# Sheet_v3.net
KiCad netlist of a schematic drawn in Altium Designer
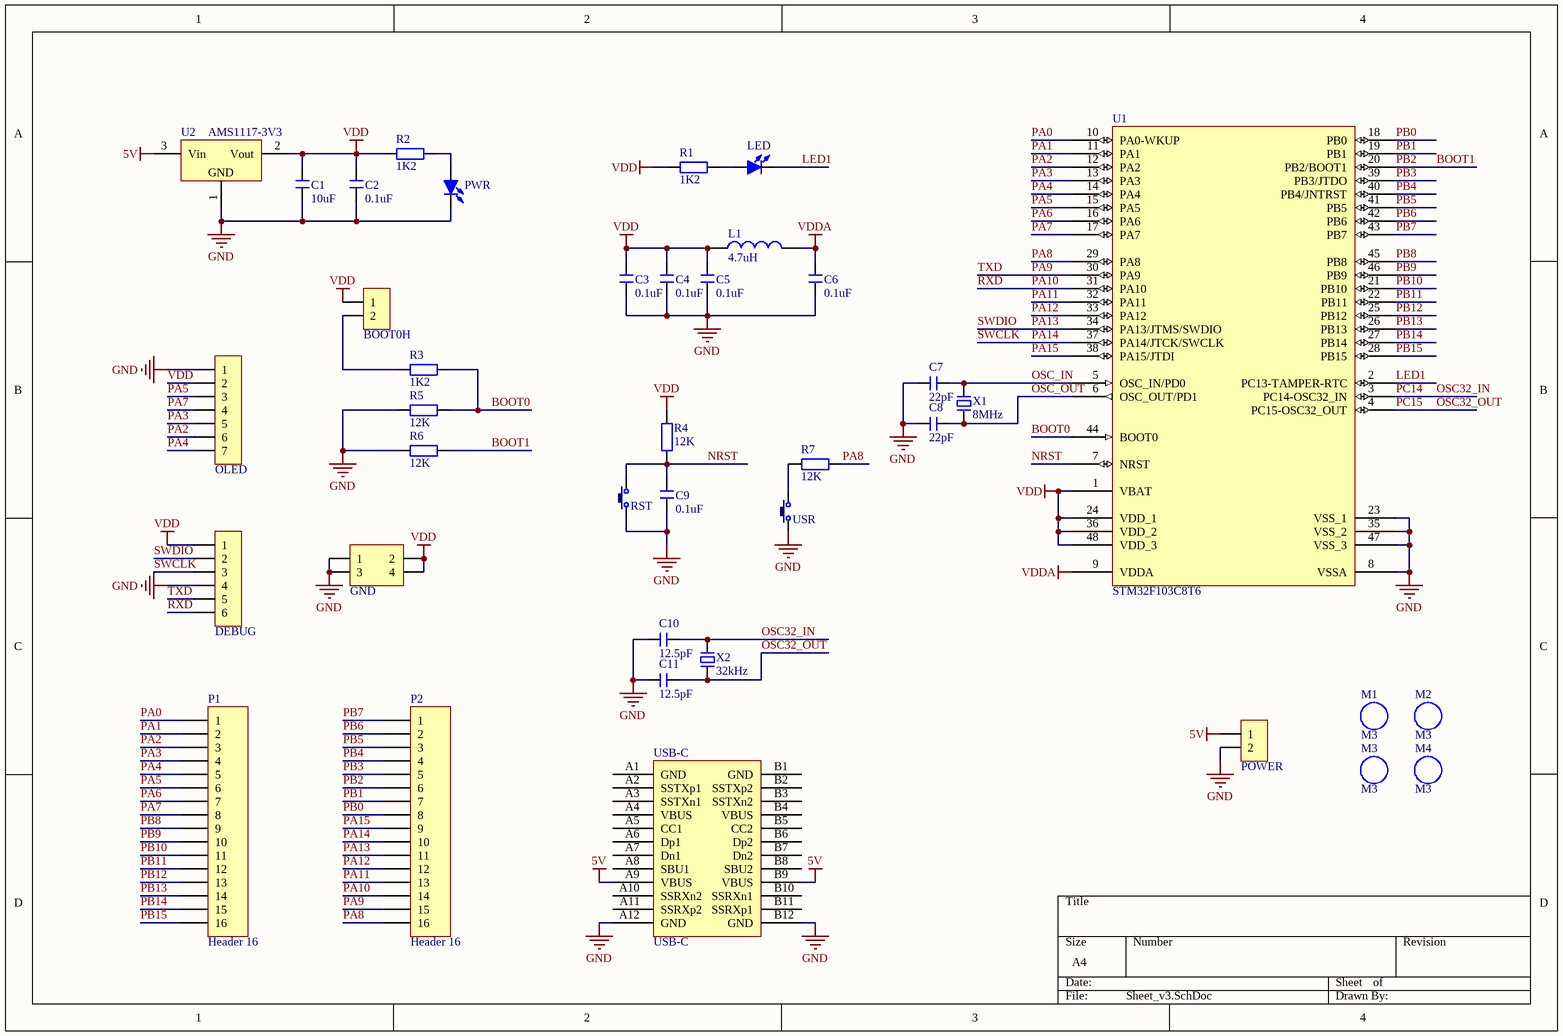
[diagram p0: Sheet_v3.SchDoc]

(export (version "E")
  (design (tool "Eeschema 10.0.6"))
  (components
    (comp (ref "BOOT0H")
      (value "HDR-1X2")
      (footprint "TSW SMD-3*4*2.5")
      (description "2P接插件")
      (fields (field (name "版权归属") "源创客"))
      (libsource (lib "接插件") (part "Header 2"))
    )
    (comp (ref "C1")
      (value "10uF")
      (footprint "C 0805")
      (description "无极性贴片电容")
      (fields (field (name "版权归属") "源创客"))
      (libsource (lib "电阻-电容-电感") (part "C"))
    )
    (comp (ref "C2")
      (value "0.1uF")
      (footprint "C 0603")
      (description "无极性贴片电容")
      (fields (field (name "版权归属") "源创客"))
      (libsource (lib "电阻-电容-电感") (part "C"))
    )
    (comp (ref "C3")
      (value "0.1uF")
      (footprint "C 0603")
      (description "无极性贴片电容")
      (fields (field (name "版权归属") "源创客"))
      (libsource (lib "电阻-电容-电感") (part "C"))
    )
    (comp (ref "C4")
      (value "0.1uF")
      (footprint "C 0603")
      (description "无极性贴片电容")
      (fields (field (name "版权归属") "源创客"))
      (libsource (lib "电阻-电容-电感") (part "C"))
    )
    (comp (ref "C5")
      (value "0.1uF")
      (footprint "C 0603")
      (description "无极性贴片电容")
      (fields (field (name "版权归属") "源创客"))
      (libsource (lib "电阻-电容-电感") (part "C"))
    )
    (comp (ref "C6")
      (value "0.1uF")
      (footprint "C 0603")
      (description "无极性贴片电容")
      (fields (field (name "版权归属") "源创客"))
      (libsource (lib "电阻-电容-电感") (part "C"))
    )
    (comp (ref "C7")
      (value "22pF")
      (footprint "C 0603")
      (description "无极性贴片电容")
      (fields (field (name "版权归属") "源创客"))
      (libsource (lib "电阻-电容-电感") (part "C"))
    )
    (comp (ref "C8")
      (value "22pF")
      (footprint "C 0603")
      (description "无极性贴片电容")
      (fields (field (name "版权归属") "源创客"))
      (libsource (lib "电阻-电容-电感") (part "C"))
    )
    (comp (ref "C9")
      (value "0.1uF")
      (footprint "C 0603")
      (description "无极性贴片电容")
      (fields (field (name "版权归属") "源创客"))
      (libsource (lib "电阻-电容-电感") (part "C"))
    )
    (comp (ref "C10")
      (value "12.5pF")
      (footprint "C 0603")
      (description "无极性贴片电容")
      (fields (field (name "版权归属") "源创客"))
      (libsource (lib "电阻-电容-电感") (part "C"))
    )
    (comp (ref "C11")
      (value "12.5pF")
      (footprint "C 0603")
      (description "无极性贴片电容")
      (fields (field (name "版权归属") "源创客"))
      (libsource (lib "电阻-电容-电感") (part "C"))
    )
    (comp (ref "DEBUG")
      (value "HDR-1X6")
      (footprint "HDR-1X6")
      (description "6P接插件")
      (fields (field (name "版权归属") "源创客"))
      (libsource (lib "接插件") (part "Header 6"))
    )
    (comp (ref "GND")
      (value "Header2X2")
      (footprint "HDR-2X2")
      (description "2*2P接插件")
      (fields (field (name "版权归属") "源创客"))
      (libsource (lib "接插件") (part "Header 2X2"))
    )
    (comp (ref "L1")
      (value "4.7uH")
      (footprint "L 0805")
      (description "小功率贴片电感")
      (fields (field (name "版权归属") "源创客"))
      (libsource (lib "电阻-电容-电感") (part "L"))
    )
    (comp (ref "LED")
      (value "~")
      (footprint "LED 0805G")
      (description "贴片LED")
      (fields (field (name "版权归属") "源创客"))
      (libsource (lib "LED") (part "LED-SMD"))
    )
    (comp (ref "M1")
      (value "M3")
      (footprint "M3 125X200")
      (description "铜柱孔")
      (fields (field (name "版权归属") "源创客"))
      (libsource (lib "未分类器件") (part "M3"))
    )
    (comp (ref "M2")
      (value "M3")
      (footprint "M3 125X200")
      (description "铜柱孔")
      (fields (field (name "版权归属") "源创客"))
      (libsource (lib "未分类器件") (part "M3"))
    )
    (comp (ref "M3")
      (value "M3")
      (footprint "M3 125X200")
      (description "铜柱孔")
      (fields (field (name "版权归属") "源创客"))
      (libsource (lib "未分类器件") (part "M3"))
    )
    (comp (ref "M4")
      (value "M3")
      (footprint "M3 125X200")
      (description "铜柱孔")
      (fields (field (name "版权归属") "源创客"))
      (libsource (lib "未分类器件") (part "M3"))
    )
    (comp (ref "OLED")
      (value "HDR-1X7")
      (footprint "HDR-1X7_M")
      (description "7P接插件")
      (fields (field (name "版权归属") "源创客"))
      (libsource (lib "接插件") (part "Header 7"))
    )
    (comp (ref "P1")
      (value "Header 16")
      (footprint "HDR1X16")
      (description "Header, 16-Pin")
      (fields (field (name "PUBLISHER") "Altium Limited"))
      (libsource (lib "Miscellaneous Connectors") (part "Header 16"))
    )
    (comp (ref "P2")
      (value "Header 16")
      (footprint "HDR1X16")
      (description "Header, 16-Pin")
      (fields (field (name "PUBLISHER") "Altium Limited"))
      (libsource (lib "Miscellaneous Connectors") (part "Header 16"))
    )
    (comp (ref "POWER")
      (value "HDR-1X2")
      (footprint "HDR-1X2")
      (description "2P接插件")
      (fields (field (name "版权归属") "源创客"))
      (libsource (lib "接插件") (part "Header 2"))
    )
    (comp (ref "PWR")
      (value "~")
      (footprint "LED 0805G")
      (description "贴片LED")
      (fields (field (name "版权归属") "源创客"))
      (libsource (lib "LED") (part "LED-SMD"))
    )
    (comp (ref "R1")
      (value "1K2")
      (footprint "R 0805")
      (description "贴片电阻")
      (fields (field (name "版权归属") "源创客"))
      (libsource (lib "电阻-电容-电感") (part "R"))
    )
    (comp (ref "R2")
      (value "1K2")
      (footprint "R 0805")
      (description "贴片电阻")
      (fields (field (name "版权归属") "源创客"))
      (libsource (lib "电阻-电容-电感") (part "R"))
    )
    (comp (ref "R3")
      (value "1K2")
      (footprint "R 0805")
      (description "贴片电阻")
      (fields (field (name "版权归属") "源创客"))
      (libsource (lib "电阻-电容-电感") (part "R"))
    )
    (comp (ref "R4")
      (value "12K")
      (footprint "R 0805")
      (description "贴片电阻")
      (fields (field (name "版权归属") "源创客"))
      (libsource (lib "电阻-电容-电感") (part "R"))
    )
    (comp (ref "R5")
      (value "12K")
      (footprint "R 0805")
      (description "贴片电阻")
      (fields (field (name "版权归属") "源创客"))
      (libsource (lib "电阻-电容-电感") (part "R"))
    )
    (comp (ref "R6")
      (value "12K")
      (footprint "R 0805")
      (description "贴片电阻")
      (fields (field (name "版权归属") "源创客"))
      (libsource (lib "电阻-电容-电感") (part "R"))
    )
    (comp (ref "R7")
      (value "12K")
      (footprint "R 0805")
      (description "贴片电阻")
      (fields (field (name "版权归属") "源创客"))
      (libsource (lib "电阻-电容-电感") (part "R"))
    )
    (comp (ref "RST")
      (value "3x6x5")
      (footprint "TSW SMD-3*6*2.5")
      (description "3x6轻触开关")
      (fields (field (name "版权归属") "源创客"))
      (libsource (lib "按键-开关") (part "TSW 3x6"))
    )
    (comp (ref "U1")
      (value "STM32F103C8T6")
      (footprint "LQFP48 7X7_M")
      (description "Flaah:64/RAM:20/IO:36")
      (fields (field (name "版权归属") "源创客"))
      (libsource (lib "STM32系列单片机") (part "STM32F103C8T6"))
    )
    (comp (ref "U2")
      (value "AMS1117-3V3")
      (footprint "SOT223_M")
      (description "三端稳压芯片")
      (fields (field (name "版权归属") "源创客"))
      (libsource (lib "IC芯片") (part "AMS1117"))
    )
    (comp (ref "USB-C")
      (value "USB-C")
      (footprint "Type_C-6P")
      (description "USB-C型母接口")
      (fields (field (name "版权归属") "源创客"))
      (libsource (lib "接口类") (part "USB-C/S"))
    )
    (comp (ref "USR")
      (value "3x6x5")
      (footprint "TSW SMD-3*6*2.5")
      (description "3x6轻触开关")
      (fields (field (name "版权归属") "源创客"))
      (libsource (lib "按键-开关") (part "TSW 3x6"))
    )
    (comp (ref "X1")
      (value "8MHz")
      (footprint "XTAL-5032_2P")
      (description "2脚晶振")
      (fields (field (name "版权归属") "源创客"))
      (libsource (lib "保险丝-晶振") (part "XTAL-2"))
    )
    (comp (ref "X2")
      (value "32kHz")
      (footprint "XTAL-3215")
      (description "2脚晶振")
      (fields (field (name "版权归属") "源创客"))
      (libsource (lib "保险丝-晶振") (part "XTAL-2"))
    )
  )
  (nets
    (net (code "1") (name "/BOOT0") (class "Default")
      (node (ref "R3") (pin "1") (pinfunction "1_1") (pintype "passive"))
      (node (ref "R5") (pin "1") (pinfunction "1_1") (pintype "passive"))
      (node (ref "U1") (pin "44") (pinfunction "BOOT0_44") (pintype "input"))
    )
    (net (code "2") (name "/BOOT1") (class "Default")
      (node (ref "P2") (pin "6") (pinfunction "6_6") (pintype "passive"))
      (node (ref "R6") (pin "1") (pinfunction "1_1") (pintype "passive"))
      (node (ref "U1") (pin "20") (pinfunction "PB2/BOOT1_20") (pintype "bidirectional"))
    )
    (net (code "3") (name "/LED1") (class "Default")
      (node (ref "LED") (pin "2") (pinfunction "K_2") (pintype "passive"))
      (node (ref "U1") (pin "2") (pinfunction "PC13-TAMPER-RTC_2") (pintype "bidirectional"))
    )
    (net (code "4") (name "/NRST") (class "Default")
      (node (ref "C9") (pin "2") (pinfunction "2_2") (pintype "passive"))
      (node (ref "R4") (pin "1") (pinfunction "1_1") (pintype "passive"))
      (node (ref "RST") (pin "2") (pinfunction "2_2") (pintype "passive"))
      (node (ref "U1") (pin "7") (pinfunction "NRST_7") (pintype "bidirectional"))
    )
    (net (code "5") (name "/OSC32_IN") (class "Default")
      (node (ref "C10") (pin "2") (pinfunction "2_2") (pintype "passive"))
      (node (ref "U1") (pin "3") (pinfunction "PC14-OSC32_IN_3") (pintype "bidirectional"))
      (node (ref "X2") (pin "2") (pinfunction "2_2") (pintype "passive"))
    )
    (net (code "6") (name "/OSC32_OUT") (class "Default")
      (node (ref "C11") (pin "2") (pinfunction "2_2") (pintype "passive"))
      (node (ref "U1") (pin "4") (pinfunction "PC15-OSC32_OUT_4") (pintype "bidirectional"))
      (node (ref "X2") (pin "1") (pinfunction "1_1") (pintype "passive"))
    )
    (net (code "7") (name "/OSC_IN") (class "Default")
      (node (ref "C7") (pin "2") (pinfunction "2_2") (pintype "passive"))
      (node (ref "U1") (pin "5") (pinfunction "OSC_IN/PD0_5") (pintype "input"))
      (node (ref "X1") (pin "2") (pinfunction "2_2") (pintype "passive"))
    )
    (net (code "8") (name "/OSC_OUT") (class "Default")
      (node (ref "C8") (pin "2") (pinfunction "2_2") (pintype "passive"))
      (node (ref "U1") (pin "6") (pinfunction "OSC_OUT/PD1_6") (pintype "output"))
      (node (ref "X1") (pin "1") (pinfunction "1_1") (pintype "passive"))
    )
    (net (code "9") (name "/PA0") (class "Default")
      (node (ref "P1") (pin "1") (pinfunction "1_1") (pintype "passive"))
      (node (ref "U1") (pin "10") (pinfunction "PA0-WKUP_10") (pintype "bidirectional"))
    )
    (net (code "10") (name "/PA1") (class "Default")
      (node (ref "P1") (pin "2") (pinfunction "2_2") (pintype "passive"))
      (node (ref "U1") (pin "11") (pinfunction "PA1_11") (pintype "bidirectional"))
    )
    (net (code "11") (name "/PA2") (class "Default")
      (node (ref "OLED") (pin "6") (pinfunction "6_6") (pintype "passive"))
      (node (ref "P1") (pin "3") (pinfunction "3_3") (pintype "passive"))
      (node (ref "U1") (pin "12") (pinfunction "PA2_12") (pintype "bidirectional"))
    )
    (net (code "12") (name "/PA3") (class "Default")
      (node (ref "OLED") (pin "5") (pinfunction "5_5") (pintype "passive"))
      (node (ref "P1") (pin "4") (pinfunction "4_4") (pintype "passive"))
      (node (ref "U1") (pin "13") (pinfunction "PA3_13") (pintype "bidirectional"))
    )
    (net (code "13") (name "/PA4") (class "Default")
      (node (ref "OLED") (pin "7") (pinfunction "7_7") (pintype "passive"))
      (node (ref "P1") (pin "5") (pinfunction "5_5") (pintype "passive"))
      (node (ref "U1") (pin "14") (pinfunction "PA4_14") (pintype "bidirectional"))
    )
    (net (code "14") (name "/PA5") (class "Default")
      (node (ref "OLED") (pin "3") (pinfunction "3_3") (pintype "passive"))
      (node (ref "P1") (pin "6") (pinfunction "6_6") (pintype "passive"))
      (node (ref "U1") (pin "15") (pinfunction "PA5_15") (pintype "bidirectional"))
    )
    (net (code "15") (name "/PA6") (class "Default")
      (node (ref "P1") (pin "7") (pinfunction "7_7") (pintype "passive"))
      (node (ref "U1") (pin "16") (pinfunction "PA6_16") (pintype "bidirectional"))
    )
    (net (code "16") (name "/PA7") (class "Default")
      (node (ref "OLED") (pin "4") (pinfunction "4_4") (pintype "passive"))
      (node (ref "P1") (pin "8") (pinfunction "8_8") (pintype "passive"))
      (node (ref "U1") (pin "17") (pinfunction "PA7_17") (pintype "bidirectional"))
    )
    (net (code "17") (name "/PA8") (class "Default")
      (node (ref "P2") (pin "16") (pinfunction "16_16") (pintype "passive"))
      (node (ref "R7") (pin "2") (pinfunction "2_2") (pintype "passive"))
      (node (ref "U1") (pin "29") (pinfunction "PA8_29") (pintype "bidirectional"))
    )
    (net (code "18") (name "/PA9") (class "Default")
      (node (ref "DEBUG") (pin "5") (pinfunction "5_5") (pintype "passive"))
      (node (ref "P2") (pin "15") (pinfunction "15_15") (pintype "passive"))
      (node (ref "U1") (pin "30") (pinfunction "PA9_30") (pintype "bidirectional"))
    )
    (net (code "19") (name "/PA10") (class "Default")
      (node (ref "DEBUG") (pin "6") (pinfunction "6_6") (pintype "passive"))
      (node (ref "P2") (pin "14") (pinfunction "14_14") (pintype "passive"))
      (node (ref "U1") (pin "31") (pinfunction "PA10_31") (pintype "bidirectional"))
    )
    (net (code "20") (name "/PA11") (class "Default")
      (node (ref "P2") (pin "13") (pinfunction "13_13") (pintype "passive"))
      (node (ref "U1") (pin "32") (pinfunction "PA11_32") (pintype "bidirectional"))
    )
    (net (code "21") (name "/PA12") (class "Default")
      (node (ref "P2") (pin "12") (pinfunction "12_12") (pintype "passive"))
      (node (ref "U1") (pin "33") (pinfunction "PA12_33") (pintype "bidirectional"))
    )
    (net (code "22") (name "/PA13") (class "Default")
      (node (ref "DEBUG") (pin "2") (pinfunction "2_2") (pintype "passive"))
      (node (ref "P2") (pin "11") (pinfunction "11_11") (pintype "passive"))
      (node (ref "U1") (pin "34") (pinfunction "PA13/JTMS/SWDIO_34") (pintype "bidirectional"))
    )
    (net (code "23") (name "/PA14") (class "Default")
      (node (ref "DEBUG") (pin "3") (pinfunction "3_3") (pintype "passive"))
      (node (ref "P2") (pin "10") (pinfunction "10_10") (pintype "passive"))
      (node (ref "U1") (pin "37") (pinfunction "PA14/JTCK/SWCLK_37") (pintype "bidirectional"))
    )
    (net (code "24") (name "/PA15") (class "Default")
      (node (ref "P2") (pin "9") (pinfunction "9_9") (pintype "passive"))
      (node (ref "U1") (pin "38") (pinfunction "PA15/JTDI_38") (pintype "bidirectional"))
    )
    (net (code "25") (name "/PB0") (class "Default")
      (node (ref "P2") (pin "8") (pinfunction "8_8") (pintype "passive"))
      (node (ref "U1") (pin "18") (pinfunction "PB0_18") (pintype "bidirectional"))
    )
    (net (code "26") (name "/PB1") (class "Default")
      (node (ref "P2") (pin "7") (pinfunction "7_7") (pintype "passive"))
      (node (ref "U1") (pin "19") (pinfunction "PB1_19") (pintype "bidirectional"))
    )
    (net (code "27") (name "/PB3") (class "Default")
      (node (ref "P2") (pin "5") (pinfunction "5_5") (pintype "passive"))
      (node (ref "U1") (pin "39") (pinfunction "PB3/JTDO_39") (pintype "bidirectional"))
    )
    (net (code "28") (name "/PB4") (class "Default")
      (node (ref "P2") (pin "4") (pinfunction "4_4") (pintype "passive"))
      (node (ref "U1") (pin "40") (pinfunction "PB4/JNTRST_40") (pintype "bidirectional"))
    )
    (net (code "29") (name "/PB5") (class "Default")
      (node (ref "P2") (pin "3") (pinfunction "3_3") (pintype "passive"))
      (node (ref "U1") (pin "41") (pinfunction "PB5_41") (pintype "bidirectional"))
    )
    (net (code "30") (name "/PB6") (class "Default")
      (node (ref "P2") (pin "2") (pinfunction "2_2") (pintype "passive"))
      (node (ref "U1") (pin "42") (pinfunction "PB6_42") (pintype "bidirectional"))
    )
    (net (code "31") (name "/PB7") (class "Default")
      (node (ref "P2") (pin "1") (pinfunction "1_1") (pintype "passive"))
      (node (ref "U1") (pin "43") (pinfunction "PB7_43") (pintype "bidirectional"))
    )
    (net (code "32") (name "/PB8") (class "Default")
      (node (ref "P1") (pin "9") (pinfunction "9_9") (pintype "passive"))
      (node (ref "U1") (pin "45") (pinfunction "PB8_45") (pintype "bidirectional"))
    )
    (net (code "33") (name "/PB9") (class "Default")
      (node (ref "P1") (pin "10") (pinfunction "10_10") (pintype "passive"))
      (node (ref "U1") (pin "46") (pinfunction "PB9_46") (pintype "bidirectional"))
    )
    (net (code "34") (name "/PB10") (class "Default")
      (node (ref "P1") (pin "11") (pinfunction "11_11") (pintype "passive"))
      (node (ref "U1") (pin "21") (pinfunction "PB10_21") (pintype "bidirectional"))
    )
    (net (code "35") (name "/PB11") (class "Default")
      (node (ref "P1") (pin "12") (pinfunction "12_12") (pintype "passive"))
      (node (ref "U1") (pin "22") (pinfunction "PB11_22") (pintype "bidirectional"))
    )
    (net (code "36") (name "/PB12") (class "Default")
      (node (ref "P1") (pin "13") (pinfunction "13_13") (pintype "passive"))
      (node (ref "U1") (pin "25") (pinfunction "PB12_25") (pintype "bidirectional"))
    )
    (net (code "37") (name "/PB13") (class "Default")
      (node (ref "P1") (pin "14") (pinfunction "14_14") (pintype "passive"))
      (node (ref "U1") (pin "26") (pinfunction "PB13_26") (pintype "bidirectional"))
    )
    (net (code "38") (name "/PB14") (class "Default")
      (node (ref "P1") (pin "15") (pinfunction "15_15") (pintype "passive"))
      (node (ref "U1") (pin "27") (pinfunction "PB14_27") (pintype "bidirectional"))
    )
    (net (code "39") (name "/PB15") (class "Default")
      (node (ref "P1") (pin "16") (pinfunction "16_16") (pintype "passive"))
      (node (ref "U1") (pin "28") (pinfunction "PB15_28") (pintype "bidirectional"))
    )
    (net (code "40") (name "5V") (class "Default")
      (node (ref "POWER") (pin "1") (pinfunction "1_1") (pintype "passive"))
      (node (ref "U2") (pin "3") (pinfunction "Vin_3") (pintype "passive"))
      (node (ref "USB-C") (pin "A9") (pinfunction "VBUS_A9") (pintype "passive"))
      (node (ref "USB-C") (pin "B9") (pinfunction "VBUS_B9") (pintype "passive"))
    )
    (net (code "41") (name "GND") (class "Default")
      (node (ref "C1") (pin "1") (pinfunction "1_1") (pintype "passive"))
      (node (ref "C10") (pin "1") (pinfunction "1_1") (pintype "passive"))
      (node (ref "C11") (pin "1") (pinfunction "1_1") (pintype "passive"))
      (node (ref "C2") (pin "1") (pinfunction "1_1") (pintype "passive"))
      (node (ref "C3") (pin "1") (pinfunction "1_1") (pintype "passive"))
      (node (ref "C4") (pin "1") (pinfunction "1_1") (pintype "passive"))
      (node (ref "C5") (pin "1") (pinfunction "1_1") (pintype "passive"))
      (node (ref "C6") (pin "1") (pinfunction "1_1") (pintype "passive"))
      (node (ref "C7") (pin "1") (pinfunction "1_1") (pintype "passive"))
      (node (ref "C8") (pin "1") (pinfunction "1_1") (pintype "passive"))
      (node (ref "C9") (pin "1") (pinfunction "1_1") (pintype "passive"))
      (node (ref "DEBUG") (pin "4") (pinfunction "4_4") (pintype "passive"))
      (node (ref "GND") (pin "1") (pinfunction "1_1") (pintype "passive"))
      (node (ref "GND") (pin "3") (pinfunction "3_3") (pintype "passive"))
      (node (ref "OLED") (pin "1") (pinfunction "1_1") (pintype "passive"))
      (node (ref "POWER") (pin "2") (pinfunction "2_2") (pintype "passive"))
      (node (ref "PWR") (pin "2") (pinfunction "K_2") (pintype "passive"))
      (node (ref "R5") (pin "2") (pinfunction "2_2") (pintype "passive"))
      (node (ref "R6") (pin "2") (pinfunction "2_2") (pintype "passive"))
      (node (ref "RST") (pin "1") (pinfunction "1_1") (pintype "passive"))
      (node (ref "U1") (pin "23") (pinfunction "VSS_1_23") (pintype "power_in"))
      (node (ref "U1") (pin "35") (pinfunction "VSS_2_35") (pintype "power_in"))
      (node (ref "U1") (pin "47") (pinfunction "VSS_3_47") (pintype "power_in"))
      (node (ref "U1") (pin "8") (pinfunction "VSSA_8") (pintype "power_in"))
      (node (ref "U2") (pin "1") (pinfunction "GND_1") (pintype "passive"))
      (node (ref "USB-C") (pin "A12") (pinfunction "GND_A12") (pintype "passive"))
      (node (ref "USB-C") (pin "B12") (pinfunction "GND_B12") (pintype "passive"))
      (node (ref "USR") (pin "1") (pinfunction "1_1") (pintype "passive"))
    )
    (net (code "42") (name "Net-(BOOT0H-Pad2)") (class "Default")
      (node (ref "BOOT0H") (pin "2") (pinfunction "2_2") (pintype "passive"))
      (node (ref "R3") (pin "2") (pinfunction "2_2") (pintype "passive"))
    )
    (net (code "43") (name "Net-(LED-A)") (class "Default")
      (node (ref "LED") (pin "1") (pinfunction "A_1") (pintype "passive"))
      (node (ref "R1") (pin "2") (pinfunction "2_2") (pintype "passive"))
    )
    (net (code "44") (name "Net-(PWR-A)") (class "Default")
      (node (ref "PWR") (pin "1") (pinfunction "A_1") (pintype "passive"))
      (node (ref "R2") (pin "2") (pinfunction "2_2") (pintype "passive"))
    )
    (net (code "45") (name "Net-(R7-Pad1)") (class "Default")
      (node (ref "R7") (pin "1") (pinfunction "1_1") (pintype "passive"))
      (node (ref "USR") (pin "2") (pinfunction "2_2") (pintype "passive"))
    )
    (net (code "46") (name "VDD") (class "Default")
      (node (ref "BOOT0H") (pin "1") (pinfunction "1_1") (pintype "passive"))
      (node (ref "C1") (pin "2") (pinfunction "2_2") (pintype "passive"))
      (node (ref "C2") (pin "2") (pinfunction "2_2") (pintype "passive"))
      (node (ref "C3") (pin "2") (pinfunction "2_2") (pintype "passive"))
      (node (ref "C4") (pin "2") (pinfunction "2_2") (pintype "passive"))
      (node (ref "C5") (pin "2") (pinfunction "2_2") (pintype "passive"))
      (node (ref "DEBUG") (pin "1") (pinfunction "1_1") (pintype "passive"))
      (node (ref "GND") (pin "2") (pinfunction "2_2") (pintype "passive"))
      (node (ref "GND") (pin "4") (pinfunction "4_4") (pintype "passive"))
      (node (ref "L1") (pin "1") (pinfunction "1_1") (pintype "passive"))
      (node (ref "OLED") (pin "2") (pinfunction "2_2") (pintype "passive"))
      (node (ref "R1") (pin "1") (pinfunction "1_1") (pintype "passive"))
      (node (ref "R2") (pin "1") (pinfunction "1_1") (pintype "passive"))
      (node (ref "R4") (pin "2") (pinfunction "2_2") (pintype "passive"))
      (node (ref "U1") (pin "1") (pinfunction "VBAT_1") (pintype "power_in"))
      (node (ref "U1") (pin "24") (pinfunction "VDD_1_24") (pintype "power_in"))
      (node (ref "U1") (pin "36") (pinfunction "VDD_2_36") (pintype "power_in"))
      (node (ref "U1") (pin "48") (pinfunction "VDD_3_48") (pintype "power_in"))
      (node (ref "U2") (pin "2") (pinfunction "Vout_2") (pintype "passive"))
    )
    (net (code "47") (name "VDDA") (class "Default")
      (node (ref "C6") (pin "2") (pinfunction "2_2") (pintype "passive"))
      (node (ref "L1") (pin "2") (pinfunction "2_2") (pintype "passive"))
      (node (ref "U1") (pin "9") (pinfunction "VDDA_9") (pintype "power_in"))
    )
    (net (code "48") (name "unconnected-(USB-C-CC1-PadA5)") (class "Default")
      (node (ref "USB-C") (pin "A5") (pinfunction "CC1_A5") (pintype "passive"))
    )
    (net (code "49") (name "unconnected-(USB-C-CC2-PadB5)") (class "Default")
      (node (ref "USB-C") (pin "B5") (pinfunction "CC2_B5") (pintype "passive"))
    )
    (net (code "50") (name "unconnected-(USB-C-Dn1-PadA7)") (class "Default")
      (node (ref "USB-C") (pin "A7") (pinfunction "Dn1_A7") (pintype "passive"))
    )
    (net (code "51") (name "unconnected-(USB-C-Dn2-PadB7)") (class "Default")
      (node (ref "USB-C") (pin "B7") (pinfunction "Dn2_B7") (pintype "passive"))
    )
    (net (code "52") (name "unconnected-(USB-C-Dp1-PadA6)") (class "Default")
      (node (ref "USB-C") (pin "A6") (pinfunction "Dp1_A6") (pintype "passive"))
    )
    (net (code "53") (name "unconnected-(USB-C-Dp2-PadB6)") (class "Default")
      (node (ref "USB-C") (pin "B6") (pinfunction "Dp2_B6") (pintype "passive"))
    )
    (net (code "54") (name "unconnected-(USB-C-GND-PadA1)") (class "Default")
      (node (ref "USB-C") (pin "A1") (pinfunction "GND_A1") (pintype "passive"))
    )
    (net (code "55") (name "unconnected-(USB-C-GND-PadB1)") (class "Default")
      (node (ref "USB-C") (pin "B1") (pinfunction "GND_B1") (pintype "passive"))
    )
    (net (code "56") (name "unconnected-(USB-C-SBU1-PadA8)") (class "Default")
      (node (ref "USB-C") (pin "A8") (pinfunction "SBU1_A8") (pintype "passive"))
    )
    (net (code "57") (name "unconnected-(USB-C-SBU2-PadB8)") (class "Default")
      (node (ref "USB-C") (pin "B8") (pinfunction "SBU2_B8") (pintype "passive"))
    )
    (net (code "58") (name "unconnected-(USB-C-SSRXn1-PadB10)") (class "Default")
      (node (ref "USB-C") (pin "B10") (pinfunction "SSRXn1_B10") (pintype "passive"))
    )
    (net (code "59") (name "unconnected-(USB-C-SSRXn2-PadA10)") (class "Default")
      (node (ref "USB-C") (pin "A10") (pinfunction "SSRXn2_A10") (pintype "passive"))
    )
    (net (code "60") (name "unconnected-(USB-C-SSRXp1-PadB11)") (class "Default")
      (node (ref "USB-C") (pin "B11") (pinfunction "SSRXp1_B11") (pintype "passive"))
    )
    (net (code "61") (name "unconnected-(USB-C-SSRXp2-PadA11)") (class "Default")
      (node (ref "USB-C") (pin "A11") (pinfunction "SSRXp2_A11") (pintype "passive"))
    )
    (net (code "62") (name "unconnected-(USB-C-SSTXn1-PadA3)") (class "Default")
      (node (ref "USB-C") (pin "A3") (pinfunction "SSTXn1_A3") (pintype "passive"))
    )
    (net (code "63") (name "unconnected-(USB-C-SSTXn2-PadB3)") (class "Default")
      (node (ref "USB-C") (pin "B3") (pinfunction "SSTXn2_B3") (pintype "passive"))
    )
    (net (code "64") (name "unconnected-(USB-C-SSTXp1-PadA2)") (class "Default")
      (node (ref "USB-C") (pin "A2") (pinfunction "SSTXp1_A2") (pintype "passive"))
    )
    (net (code "65") (name "unconnected-(USB-C-SSTXp2-PadB2)") (class "Default")
      (node (ref "USB-C") (pin "B2") (pinfunction "SSTXp2_B2") (pintype "passive"))
    )
    (net (code "66") (name "unconnected-(USB-C-VBUS-PadA4)") (class "Default")
      (node (ref "USB-C") (pin "A4") (pinfunction "VBUS_A4") (pintype "passive"))
    )
    (net (code "67") (name "unconnected-(USB-C-VBUS-PadB4)") (class "Default")
      (node (ref "USB-C") (pin "B4") (pinfunction "VBUS_B4") (pintype "passive"))
    )
  )
)
